# masterBoard1.net
KiCad netlist of a schematic drawn in EAGLE
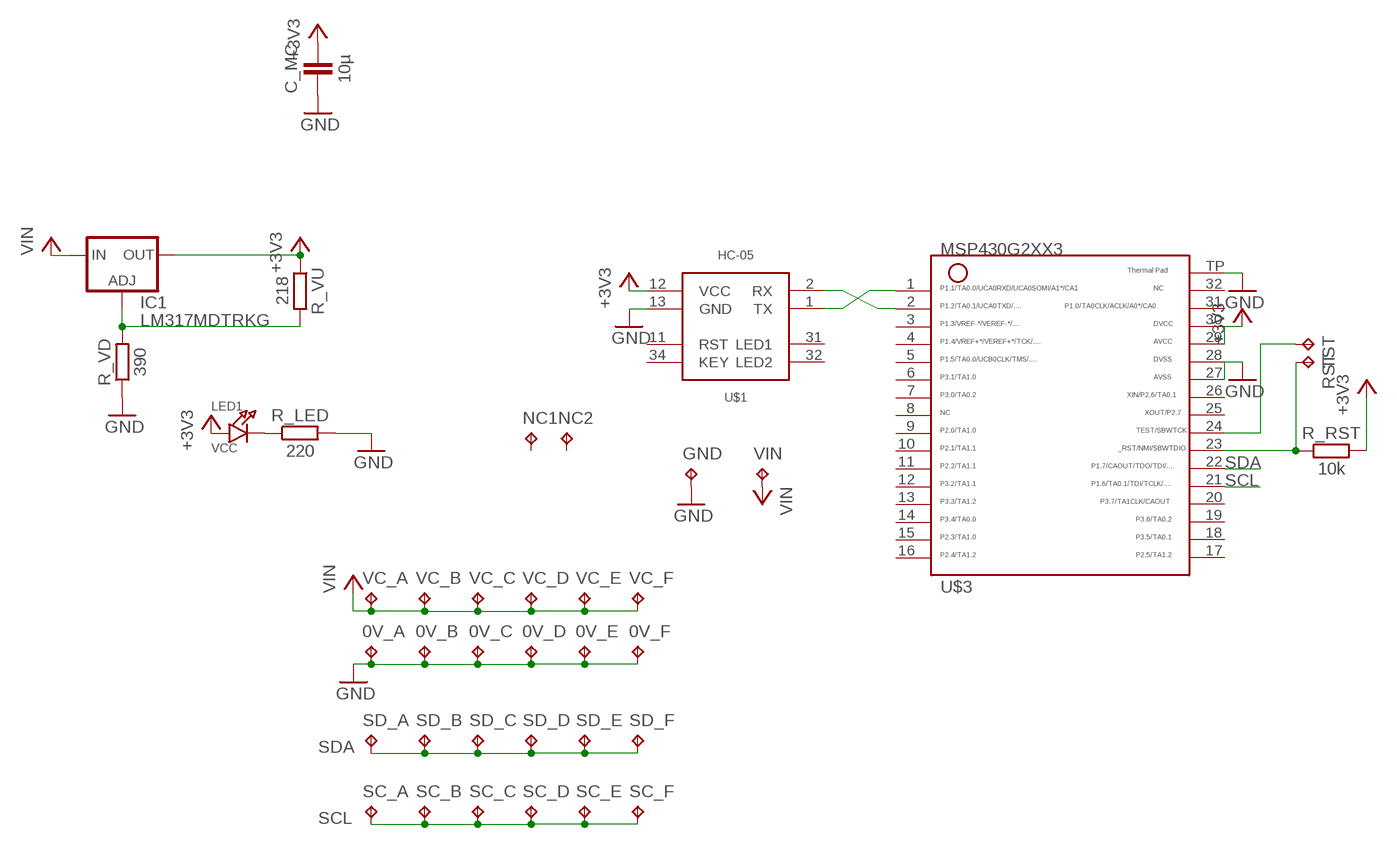
[diagram p0: schematic, sheet 1]

(export (version "E")
  (design (tool "Eeschema 10.0.6"))
  (components
    (comp (ref "0V_A")
      (value "TPTP15SQ")
      (footprint "eagle-import:TP15SQ")
      (libsource (lib "eagle-import") (part "TPTP15SQ"))
    )
    (comp (ref "0V_B")
      (value "TPTP15SQ")
      (footprint "eagle-import:TP15SQ")
      (libsource (lib "eagle-import") (part "TPTP15SQ"))
    )
    (comp (ref "0V_C")
      (value "TPTP15SQ")
      (footprint "eagle-import:TP15SQ")
      (libsource (lib "eagle-import") (part "TPTP15SQ"))
    )
    (comp (ref "0V_D")
      (value "TPTP15SQ")
      (footprint "eagle-import:TP15SQ")
      (libsource (lib "eagle-import") (part "TPTP15SQ"))
    )
    (comp (ref "0V_E")
      (value "TPTP15SQ")
      (footprint "eagle-import:TP15SQ")
      (libsource (lib "eagle-import") (part "TPTP15SQ"))
    )
    (comp (ref "0V_F")
      (value "TPTP15SQ")
      (footprint "eagle-import:TP15SQ")
      (libsource (lib "eagle-import") (part "TPTP15SQ"))
    )
    (comp (ref "C_MC")
      (value "10µ")
      (footprint "eagle-import:603")
      (libsource (lib "eagle-import") (part "CAPACITOR"))
    )
    (comp (ref "GND")
      (value "TPTP15SQ")
      (footprint "eagle-import:TP15SQ")
      (libsource (lib "eagle-import") (part "TPTP15SQ"))
    )
    (comp (ref "IC1")
      (value "LM317MDTRKG")
      (footprint "eagle-import:DPACK")
      (libsource (lib "eagle-import") (part "LM317?MDTRKG"))
    )
    (comp (ref "LED1")
      (value "VCC")
      (footprint "eagle-import:CHIPLED_0805")
      (libsource (lib "eagle-import") (part "LED0805"))
    )
    (comp (ref "NC1")
      (value "TPTP15SQ")
      (footprint "eagle-import:TP15SQ")
      (libsource (lib "eagle-import") (part "TPTP15SQ"))
    )
    (comp (ref "NC2")
      (value "TPTP15SQ")
      (footprint "eagle-import:TP15SQ")
      (libsource (lib "eagle-import") (part "TPTP15SQ"))
    )
    (comp (ref "RST")
      (value "TPTP15SQ")
      (footprint "eagle-import:TP15SQ")
      (libsource (lib "eagle-import") (part "TPTP15SQ"))
    )
    (comp (ref "R_LED")
      (value "220")
      (footprint "eagle-import:603")
      (libsource (lib "eagle-import") (part "RESISTOR0603"))
    )
    (comp (ref "R_RST")
      (value "10k")
      (footprint "eagle-import:603")
      (libsource (lib "eagle-import") (part "RESISTOR0603"))
    )
    (comp (ref "R_VD")
      (value "390")
      (footprint "eagle-import:603")
      (libsource (lib "eagle-import") (part "RESISTOR0603"))
    )
    (comp (ref "R_VU")
      (value "218")
      (footprint "eagle-import:603")
      (libsource (lib "eagle-import") (part "RESISTOR0603"))
    )
    (comp (ref "SC_A")
      (value "TPTP15SQ")
      (footprint "eagle-import:TP15SQ")
      (libsource (lib "eagle-import") (part "TPTP15SQ"))
    )
    (comp (ref "SC_B")
      (value "TPTP15SQ")
      (footprint "eagle-import:TP15SQ")
      (libsource (lib "eagle-import") (part "TPTP15SQ"))
    )
    (comp (ref "SC_C")
      (value "TPTP15SQ")
      (footprint "eagle-import:TP15SQ")
      (libsource (lib "eagle-import") (part "TPTP15SQ"))
    )
    (comp (ref "SC_D")
      (value "TPTP15SQ")
      (footprint "eagle-import:TP15SQ")
      (libsource (lib "eagle-import") (part "TPTP15SQ"))
    )
    (comp (ref "SC_E")
      (value "TPTP15SQ")
      (footprint "eagle-import:TP15SQ")
      (libsource (lib "eagle-import") (part "TPTP15SQ"))
    )
    (comp (ref "SC_F")
      (value "TPTP15SQ")
      (footprint "eagle-import:TP15SQ")
      (libsource (lib "eagle-import") (part "TPTP15SQ"))
    )
    (comp (ref "SD_A")
      (value "TPTP15SQ")
      (footprint "eagle-import:TP15SQ")
      (libsource (lib "eagle-import") (part "TPTP15SQ"))
    )
    (comp (ref "SD_B")
      (value "TPTP15SQ")
      (footprint "eagle-import:TP15SQ")
      (libsource (lib "eagle-import") (part "TPTP15SQ"))
    )
    (comp (ref "SD_C")
      (value "TPTP15SQ")
      (footprint "eagle-import:TP15SQ")
      (libsource (lib "eagle-import") (part "TPTP15SQ"))
    )
    (comp (ref "SD_D")
      (value "TPTP15SQ")
      (footprint "eagle-import:TP15SQ")
      (libsource (lib "eagle-import") (part "TPTP15SQ"))
    )
    (comp (ref "SD_E")
      (value "TPTP15SQ")
      (footprint "eagle-import:TP15SQ")
      (libsource (lib "eagle-import") (part "TPTP15SQ"))
    )
    (comp (ref "SD_F")
      (value "TPTP15SQ")
      (footprint "eagle-import:TP15SQ")
      (libsource (lib "eagle-import") (part "TPTP15SQ"))
    )
    (comp (ref "TST")
      (value "TPTP15SQ")
      (footprint "eagle-import:TP15SQ")
      (libsource (lib "eagle-import") (part "TPTP15SQ"))
    )
    (comp (ref "U$1")
      (value "HC-05")
      (footprint "eagle-import:HC-06")
      (libsource (lib "eagle-import") (part "HC-05"))
    )
    (comp (ref "U$3")
      (value "G2XX3---RHB32")
      (footprint "eagle-import:RHB32")
      (libsource (lib "eagle-import") (part "G2XX3---RHB32"))
    )
    (comp (ref "VC_A")
      (value "TPTP15SQ")
      (footprint "eagle-import:TP15SQ")
      (libsource (lib "eagle-import") (part "TPTP15SQ"))
    )
    (comp (ref "VC_B")
      (value "TPTP15SQ")
      (footprint "eagle-import:TP15SQ")
      (libsource (lib "eagle-import") (part "TPTP15SQ"))
    )
    (comp (ref "VC_C")
      (value "TPTP15SQ")
      (footprint "eagle-import:TP15SQ")
      (libsource (lib "eagle-import") (part "TPTP15SQ"))
    )
    (comp (ref "VC_D")
      (value "TPTP15SQ")
      (footprint "eagle-import:TP15SQ")
      (libsource (lib "eagle-import") (part "TPTP15SQ"))
    )
    (comp (ref "VC_E")
      (value "TPTP15SQ")
      (footprint "eagle-import:TP15SQ")
      (libsource (lib "eagle-import") (part "TPTP15SQ"))
    )
    (comp (ref "VC_F")
      (value "TPTP15SQ")
      (footprint "eagle-import:TP15SQ")
      (libsource (lib "eagle-import") (part "TPTP15SQ"))
    )
    (comp (ref "VIN")
      (value "TPTP15SQ")
      (footprint "eagle-import:TP15SQ")
      (libsource (lib "eagle-import") (part "TPTP15SQ"))
    )
  )
  (nets
    (net (code "1") (name "+3V3") (class "Default")
      (node (ref "C_MC") (pin "2") (pinfunction "2_2") (pintype "passive"))
      (node (ref "IC1") (pin "4") (pinfunction "OUT_4") (pintype "passive"))
      (node (ref "LED1") (pin "A") (pinfunction "A_A") (pintype "passive"))
      (node (ref "R_RST") (pin "2") (pinfunction "2_2") (pintype "passive"))
      (node (ref "R_VU") (pin "1") (pinfunction "1_1") (pintype "passive"))
      (node (ref "U$1") (pin "12") (pinfunction "VCC_12") (pintype "bidirectional"))
      (node (ref "U$3") (pin "29") (pinfunction "29_29") (pintype "bidirectional"))
      (node (ref "U$3") (pin "30") (pinfunction "30_30") (pintype "bidirectional"))
    )
    (net (code "2") (name "/SCL") (class "Default")
      (node (ref "SC_A") (pin "TP") (pinfunction "TP_TP") (pintype "input"))
      (node (ref "SC_B") (pin "TP") (pinfunction "TP_TP") (pintype "input"))
      (node (ref "SC_C") (pin "TP") (pinfunction "TP_TP") (pintype "input"))
      (node (ref "SC_D") (pin "TP") (pinfunction "TP_TP") (pintype "input"))
      (node (ref "SC_E") (pin "TP") (pinfunction "TP_TP") (pintype "input"))
      (node (ref "SC_F") (pin "TP") (pinfunction "TP_TP") (pintype "input"))
      (node (ref "U$3") (pin "21") (pinfunction "21_21") (pintype "bidirectional"))
    )
    (net (code "3") (name "/SDA") (class "Default")
      (node (ref "SD_A") (pin "TP") (pinfunction "TP_TP") (pintype "input"))
      (node (ref "SD_B") (pin "TP") (pinfunction "TP_TP") (pintype "input"))
      (node (ref "SD_C") (pin "TP") (pinfunction "TP_TP") (pintype "input"))
      (node (ref "SD_D") (pin "TP") (pinfunction "TP_TP") (pintype "input"))
      (node (ref "SD_E") (pin "TP") (pinfunction "TP_TP") (pintype "input"))
      (node (ref "SD_F") (pin "TP") (pinfunction "TP_TP") (pintype "input"))
      (node (ref "U$3") (pin "22") (pinfunction "22_22") (pintype "bidirectional"))
    )
    (net (code "4") (name "GND") (class "Default")
      (node (ref "0V_A") (pin "TP") (pinfunction "TP_TP") (pintype "input"))
      (node (ref "0V_B") (pin "TP") (pinfunction "TP_TP") (pintype "input"))
      (node (ref "0V_C") (pin "TP") (pinfunction "TP_TP") (pintype "input"))
      (node (ref "0V_D") (pin "TP") (pinfunction "TP_TP") (pintype "input"))
      (node (ref "0V_E") (pin "TP") (pinfunction "TP_TP") (pintype "input"))
      (node (ref "0V_F") (pin "TP") (pinfunction "TP_TP") (pintype "input"))
      (node (ref "C_MC") (pin "1") (pinfunction "1_1") (pintype "passive"))
      (node (ref "GND") (pin "TP") (pinfunction "TP_TP") (pintype "input"))
      (node (ref "R_LED") (pin "2") (pinfunction "2_2") (pintype "passive"))
      (node (ref "R_VD") (pin "1") (pinfunction "1_1") (pintype "passive"))
      (node (ref "U$1") (pin "13") (pinfunction "GND_13") (pintype "bidirectional"))
      (node (ref "U$3") (pin "27") (pinfunction "27_27") (pintype "bidirectional"))
      (node (ref "U$3") (pin "28") (pinfunction "28_28") (pintype "bidirectional"))
      (node (ref "U$3") (pin "TP") (pinfunction "TP_TP") (pintype "bidirectional"))
    )
    (net (code "5") (name "Net-(IC1-ADJ)") (class "Default")
      (node (ref "IC1") (pin "1") (pinfunction "ADJ_1") (pintype "input"))
      (node (ref "R_VD") (pin "2") (pinfunction "2_2") (pintype "passive"))
      (node (ref "R_VU") (pin "2") (pinfunction "2_2") (pintype "passive"))
    )
    (net (code "6") (name "Net-(LED1-PadC)") (class "Default")
      (node (ref "LED1") (pin "C") (pinfunction "C_C") (pintype "passive"))
      (node (ref "R_LED") (pin "1") (pinfunction "1_1") (pintype "passive"))
    )
    (net (code "7") (name "Net-(RST-PadTP)") (class "Default")
      (node (ref "RST") (pin "TP") (pinfunction "TP_TP") (pintype "input"))
      (node (ref "R_RST") (pin "1") (pinfunction "1_1") (pintype "passive"))
      (node (ref "U$3") (pin "23") (pinfunction "23_23") (pintype "bidirectional"))
    )
    (net (code "8") (name "Net-(TST-PadTP)") (class "Default")
      (node (ref "TST") (pin "TP") (pinfunction "TP_TP") (pintype "input"))
      (node (ref "U$3") (pin "24") (pinfunction "24_24") (pintype "bidirectional"))
    )
    (net (code "9") (name "Net-(U$1-RX)") (class "Default")
      (node (ref "U$1") (pin "2") (pinfunction "RX_2") (pintype "bidirectional"))
      (node (ref "U$3") (pin "2") (pinfunction "2_2") (pintype "bidirectional"))
    )
    (net (code "10") (name "Net-(U$1-TX)") (class "Default")
      (node (ref "U$1") (pin "1") (pinfunction "TX_1") (pintype "bidirectional"))
      (node (ref "U$3") (pin "1") (pinfunction "1_1") (pintype "bidirectional"))
    )
    (net (code "11") (name "VIN") (class "Default")
      (node (ref "IC1") (pin "3") (pinfunction "IN_3") (pintype "input"))
      (node (ref "VC_A") (pin "TP") (pinfunction "TP_TP") (pintype "input"))
      (node (ref "VC_B") (pin "TP") (pinfunction "TP_TP") (pintype "input"))
      (node (ref "VC_C") (pin "TP") (pinfunction "TP_TP") (pintype "input"))
      (node (ref "VC_D") (pin "TP") (pinfunction "TP_TP") (pintype "input"))
      (node (ref "VC_E") (pin "TP") (pinfunction "TP_TP") (pintype "input"))
      (node (ref "VC_F") (pin "TP") (pinfunction "TP_TP") (pintype "input"))
      (node (ref "VIN") (pin "TP") (pinfunction "TP_TP") (pintype "input"))
    )
    (net (code "12") (name "unconnected-(NC1-PadTP)") (class "Default")
      (node (ref "NC1") (pin "TP") (pinfunction "TP_TP") (pintype "input"))
    )
    (net (code "13") (name "unconnected-(NC2-PadTP)") (class "Default")
      (node (ref "NC2") (pin "TP") (pinfunction "TP_TP") (pintype "input"))
    )
    (net (code "14") (name "unconnected-(U$1-KEY-Pad34)") (class "Default")
      (node (ref "U$1") (pin "34") (pinfunction "KEY_34") (pintype "bidirectional"))
    )
    (net (code "15") (name "unconnected-(U$1-LED1-Pad31)") (class "Default")
      (node (ref "U$1") (pin "31") (pinfunction "LED1_31") (pintype "bidirectional"))
    )
    (net (code "16") (name "unconnected-(U$1-LED2-Pad32)") (class "Default")
      (node (ref "U$1") (pin "32") (pinfunction "LED2_32") (pintype "bidirectional"))
    )
    (net (code "17") (name "unconnected-(U$1-RST-Pad11)") (class "Default")
      (node (ref "U$1") (pin "11") (pinfunction "RST_11") (pintype "bidirectional"))
    )
    (net (code "18") (name "unconnected-(U$3-Pad3)") (class "Default")
      (node (ref "U$3") (pin "3") (pinfunction "3_3") (pintype "bidirectional"))
    )
    (net (code "19") (name "unconnected-(U$3-Pad4)") (class "Default")
      (node (ref "U$3") (pin "4") (pinfunction "4_4") (pintype "bidirectional"))
    )
    (net (code "20") (name "unconnected-(U$3-Pad5)") (class "Default")
      (node (ref "U$3") (pin "5") (pinfunction "5_5") (pintype "bidirectional"))
    )
    (net (code "21") (name "unconnected-(U$3-Pad6)") (class "Default")
      (node (ref "U$3") (pin "6") (pinfunction "6_6") (pintype "bidirectional"))
    )
    (net (code "22") (name "unconnected-(U$3-Pad7)") (class "Default")
      (node (ref "U$3") (pin "7") (pinfunction "7_7") (pintype "bidirectional"))
    )
    (net (code "23") (name "unconnected-(U$3-Pad8)") (class "Default")
      (node (ref "U$3") (pin "8") (pinfunction "8_8") (pintype "bidirectional"))
    )
    (net (code "24") (name "unconnected-(U$3-Pad9)") (class "Default")
      (node (ref "U$3") (pin "9") (pinfunction "9_9") (pintype "bidirectional"))
    )
    (net (code "25") (name "unconnected-(U$3-Pad10)") (class "Default")
      (node (ref "U$3") (pin "10") (pinfunction "10_10") (pintype "bidirectional"))
    )
    (net (code "26") (name "unconnected-(U$3-Pad11)") (class "Default")
      (node (ref "U$3") (pin "11") (pinfunction "11_11") (pintype "bidirectional"))
    )
    (net (code "27") (name "unconnected-(U$3-Pad12)") (class "Default")
      (node (ref "U$3") (pin "12") (pinfunction "12_12") (pintype "bidirectional"))
    )
    (net (code "28") (name "unconnected-(U$3-Pad13)") (class "Default")
      (node (ref "U$3") (pin "13") (pinfunction "13_13") (pintype "bidirectional"))
    )
    (net (code "29") (name "unconnected-(U$3-Pad14)") (class "Default")
      (node (ref "U$3") (pin "14") (pinfunction "14_14") (pintype "bidirectional"))
    )
    (net (code "30") (name "unconnected-(U$3-Pad15)") (class "Default")
      (node (ref "U$3") (pin "15") (pinfunction "15_15") (pintype "bidirectional"))
    )
    (net (code "31") (name "unconnected-(U$3-Pad16)") (class "Default")
      (node (ref "U$3") (pin "16") (pinfunction "16_16") (pintype "bidirectional"))
    )
    (net (code "32") (name "unconnected-(U$3-Pad17)") (class "Default")
      (node (ref "U$3") (pin "17") (pinfunction "17_17") (pintype "bidirectional"))
    )
    (net (code "33") (name "unconnected-(U$3-Pad18)") (class "Default")
      (node (ref "U$3") (pin "18") (pinfunction "18_18") (pintype "bidirectional"))
    )
    (net (code "34") (name "unconnected-(U$3-Pad19)") (class "Default")
      (node (ref "U$3") (pin "19") (pinfunction "19_19") (pintype "bidirectional"))
    )
    (net (code "35") (name "unconnected-(U$3-Pad20)") (class "Default")
      (node (ref "U$3") (pin "20") (pinfunction "20_20") (pintype "bidirectional"))
    )
    (net (code "36") (name "unconnected-(U$3-Pad25)") (class "Default")
      (node (ref "U$3") (pin "25") (pinfunction "25_25") (pintype "bidirectional"))
    )
    (net (code "37") (name "unconnected-(U$3-Pad26)") (class "Default")
      (node (ref "U$3") (pin "26") (pinfunction "26_26") (pintype "bidirectional"))
    )
    (net (code "38") (name "unconnected-(U$3-Pad31)") (class "Default")
      (node (ref "U$3") (pin "31") (pinfunction "31_31") (pintype "bidirectional"))
    )
    (net (code "39") (name "unconnected-(U$3-Pad32)") (class "Default")
      (node (ref "U$3") (pin "32") (pinfunction "32_32") (pintype "bidirectional"))
    )
  )
)
